# Decoup_Cap_1.net
KiCad netlist of a schematic drawn in Altium Designer
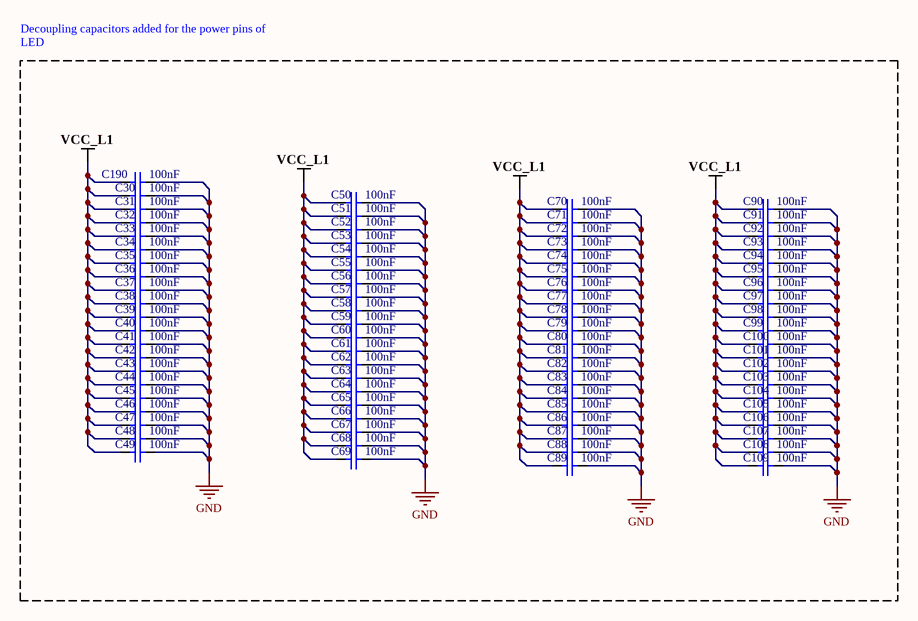
[diagram p0: Decoup_Cap 1.SchDoc]

(export (version "E")
  (design (tool "Eeschema 10.0.6"))
  (components
    (comp (ref "C30")
      (value "100nF")
      (footprint "Cap0402")
      (description "CAP CER 0.1UF 25V X7R 0402")
      (fields
        (field (name "MANUFACTURER") "Yageo")
        (field (name "MANUFACTURER PART NUMBER") "CC0402KRX7R8BB104")
      )
      (libsource (lib "TT_IntLib") (part "CC0402KRX7R8BB104"))
    )
    (comp (ref "C31")
      (value "100nF")
      (footprint "Cap0402")
      (description "CAP CER 0.1UF 25V X7R 0402")
      (fields
        (field (name "MANUFACTURER") "Yageo")
        (field (name "MANUFACTURER PART NUMBER") "CC0402KRX7R8BB104")
      )
      (libsource (lib "TT_IntLib") (part "CC0402KRX7R8BB104"))
    )
    (comp (ref "C32")
      (value "100nF")
      (footprint "Cap0402")
      (description "CAP CER 0.1UF 25V X7R 0402")
      (fields
        (field (name "MANUFACTURER") "Yageo")
        (field (name "MANUFACTURER PART NUMBER") "CC0402KRX7R8BB104")
      )
      (libsource (lib "TT_IntLib") (part "CC0402KRX7R8BB104"))
    )
    (comp (ref "C33")
      (value "100nF")
      (footprint "Cap0402")
      (description "CAP CER 0.1UF 25V X7R 0402")
      (fields
        (field (name "MANUFACTURER") "Yageo")
        (field (name "MANUFACTURER PART NUMBER") "CC0402KRX7R8BB104")
      )
      (libsource (lib "TT_IntLib") (part "CC0402KRX7R8BB104"))
    )
    (comp (ref "C34")
      (value "100nF")
      (footprint "Cap0402")
      (description "CAP CER 0.1UF 25V X7R 0402")
      (fields
        (field (name "MANUFACTURER") "Yageo")
        (field (name "MANUFACTURER PART NUMBER") "CC0402KRX7R8BB104")
      )
      (libsource (lib "TT_IntLib") (part "CC0402KRX7R8BB104"))
    )
    (comp (ref "C35")
      (value "100nF")
      (footprint "Cap0402")
      (description "CAP CER 0.1UF 25V X7R 0402")
      (fields
        (field (name "MANUFACTURER") "Yageo")
        (field (name "MANUFACTURER PART NUMBER") "CC0402KRX7R8BB104")
      )
      (libsource (lib "TT_IntLib") (part "CC0402KRX7R8BB104"))
    )
    (comp (ref "C36")
      (value "100nF")
      (footprint "Cap0402")
      (description "CAP CER 0.1UF 25V X7R 0402")
      (fields
        (field (name "MANUFACTURER") "Yageo")
        (field (name "MANUFACTURER PART NUMBER") "CC0402KRX7R8BB104")
      )
      (libsource (lib "TT_IntLib") (part "CC0402KRX7R8BB104"))
    )
    (comp (ref "C37")
      (value "100nF")
      (footprint "Cap0402")
      (description "CAP CER 0.1UF 25V X7R 0402")
      (fields
        (field (name "MANUFACTURER") "Yageo")
        (field (name "MANUFACTURER PART NUMBER") "CC0402KRX7R8BB104")
      )
      (libsource (lib "TT_IntLib") (part "CC0402KRX7R8BB104"))
    )
    (comp (ref "C38")
      (value "100nF")
      (footprint "Cap0402")
      (description "CAP CER 0.1UF 25V X7R 0402")
      (fields
        (field (name "MANUFACTURER") "Yageo")
        (field (name "MANUFACTURER PART NUMBER") "CC0402KRX7R8BB104")
      )
      (libsource (lib "TT_IntLib") (part "CC0402KRX7R8BB104"))
    )
    (comp (ref "C39")
      (value "100nF")
      (footprint "Cap0402")
      (description "CAP CER 0.1UF 25V X7R 0402")
      (fields
        (field (name "MANUFACTURER") "Yageo")
        (field (name "MANUFACTURER PART NUMBER") "CC0402KRX7R8BB104")
      )
      (libsource (lib "TT_IntLib") (part "CC0402KRX7R8BB104"))
    )
    (comp (ref "C40")
      (value "100nF")
      (footprint "Cap0402")
      (description "CAP CER 0.1UF 25V X7R 0402")
      (fields
        (field (name "MANUFACTURER") "Yageo")
        (field (name "MANUFACTURER PART NUMBER") "CC0402KRX7R8BB104")
      )
      (libsource (lib "TT_IntLib") (part "CC0402KRX7R8BB104"))
    )
    (comp (ref "C41")
      (value "100nF")
      (footprint "Cap0402")
      (description "CAP CER 0.1UF 25V X7R 0402")
      (fields
        (field (name "MANUFACTURER") "Yageo")
        (field (name "MANUFACTURER PART NUMBER") "CC0402KRX7R8BB104")
      )
      (libsource (lib "TT_IntLib") (part "CC0402KRX7R8BB104"))
    )
    (comp (ref "C42")
      (value "100nF")
      (footprint "Cap0402")
      (description "CAP CER 0.1UF 25V X7R 0402")
      (fields
        (field (name "MANUFACTURER") "Yageo")
        (field (name "MANUFACTURER PART NUMBER") "CC0402KRX7R8BB104")
      )
      (libsource (lib "TT_IntLib") (part "CC0402KRX7R8BB104"))
    )
    (comp (ref "C43")
      (value "100nF")
      (footprint "Cap0402")
      (description "CAP CER 0.1UF 25V X7R 0402")
      (fields
        (field (name "MANUFACTURER") "Yageo")
        (field (name "MANUFACTURER PART NUMBER") "CC0402KRX7R8BB104")
      )
      (libsource (lib "TT_IntLib") (part "CC0402KRX7R8BB104"))
    )
    (comp (ref "C44")
      (value "100nF")
      (footprint "Cap0402")
      (description "CAP CER 0.1UF 25V X7R 0402")
      (fields
        (field (name "MANUFACTURER") "Yageo")
        (field (name "MANUFACTURER PART NUMBER") "CC0402KRX7R8BB104")
      )
      (libsource (lib "TT_IntLib") (part "CC0402KRX7R8BB104"))
    )
    (comp (ref "C45")
      (value "100nF")
      (footprint "Cap0402")
      (description "CAP CER 0.1UF 25V X7R 0402")
      (fields
        (field (name "MANUFACTURER") "Yageo")
        (field (name "MANUFACTURER PART NUMBER") "CC0402KRX7R8BB104")
      )
      (libsource (lib "TT_IntLib") (part "CC0402KRX7R8BB104"))
    )
    (comp (ref "C46")
      (value "100nF")
      (footprint "Cap0402")
      (description "CAP CER 0.1UF 25V X7R 0402")
      (fields
        (field (name "MANUFACTURER") "Yageo")
        (field (name "MANUFACTURER PART NUMBER") "CC0402KRX7R8BB104")
      )
      (libsource (lib "TT_IntLib") (part "CC0402KRX7R8BB104"))
    )
    (comp (ref "C47")
      (value "100nF")
      (footprint "Cap0402")
      (description "CAP CER 0.1UF 25V X7R 0402")
      (fields
        (field (name "MANUFACTURER") "Yageo")
        (field (name "MANUFACTURER PART NUMBER") "CC0402KRX7R8BB104")
      )
      (libsource (lib "TT_IntLib") (part "CC0402KRX7R8BB104"))
    )
    (comp (ref "C48")
      (value "100nF")
      (footprint "Cap0402")
      (description "CAP CER 0.1UF 25V X7R 0402")
      (fields
        (field (name "MANUFACTURER") "Yageo")
        (field (name "MANUFACTURER PART NUMBER") "CC0402KRX7R8BB104")
      )
      (libsource (lib "TT_IntLib") (part "CC0402KRX7R8BB104"))
    )
    (comp (ref "C49")
      (value "100nF")
      (footprint "Cap0402")
      (description "CAP CER 0.1UF 25V X7R 0402")
      (fields
        (field (name "MANUFACTURER") "Yageo")
        (field (name "MANUFACTURER PART NUMBER") "CC0402KRX7R8BB104")
      )
      (libsource (lib "TT_IntLib") (part "CC0402KRX7R8BB104"))
    )
    (comp (ref "C50")
      (value "100nF")
      (footprint "Cap0402")
      (description "CAP CER 0.1UF 25V X7R 0402")
      (fields
        (field (name "MANUFACTURER") "Yageo")
        (field (name "MANUFACTURER PART NUMBER") "CC0402KRX7R8BB104")
      )
      (libsource (lib "TT_IntLib") (part "CC0402KRX7R8BB104"))
    )
    (comp (ref "C51")
      (value "100nF")
      (footprint "Cap0402")
      (description "CAP CER 0.1UF 25V X7R 0402")
      (fields
        (field (name "MANUFACTURER") "Yageo")
        (field (name "MANUFACTURER PART NUMBER") "CC0402KRX7R8BB104")
      )
      (libsource (lib "TT_IntLib") (part "CC0402KRX7R8BB104"))
    )
    (comp (ref "C52")
      (value "100nF")
      (footprint "Cap0402")
      (description "CAP CER 0.1UF 25V X7R 0402")
      (fields
        (field (name "MANUFACTURER") "Yageo")
        (field (name "MANUFACTURER PART NUMBER") "CC0402KRX7R8BB104")
      )
      (libsource (lib "TT_IntLib") (part "CC0402KRX7R8BB104"))
    )
    (comp (ref "C53")
      (value "100nF")
      (footprint "Cap0402")
      (description "CAP CER 0.1UF 25V X7R 0402")
      (fields
        (field (name "MANUFACTURER") "Yageo")
        (field (name "MANUFACTURER PART NUMBER") "CC0402KRX7R8BB104")
      )
      (libsource (lib "TT_IntLib") (part "CC0402KRX7R8BB104"))
    )
    (comp (ref "C54")
      (value "100nF")
      (footprint "Cap0402")
      (description "CAP CER 0.1UF 25V X7R 0402")
      (fields
        (field (name "MANUFACTURER") "Yageo")
        (field (name "MANUFACTURER PART NUMBER") "CC0402KRX7R8BB104")
      )
      (libsource (lib "TT_IntLib") (part "CC0402KRX7R8BB104"))
    )
    (comp (ref "C55")
      (value "100nF")
      (footprint "Cap0402")
      (description "CAP CER 0.1UF 25V X7R 0402")
      (fields
        (field (name "MANUFACTURER") "Yageo")
        (field (name "MANUFACTURER PART NUMBER") "CC0402KRX7R8BB104")
      )
      (libsource (lib "TT_IntLib") (part "CC0402KRX7R8BB104"))
    )
    (comp (ref "C56")
      (value "100nF")
      (footprint "Cap0402")
      (description "CAP CER 0.1UF 25V X7R 0402")
      (fields
        (field (name "MANUFACTURER") "Yageo")
        (field (name "MANUFACTURER PART NUMBER") "CC0402KRX7R8BB104")
      )
      (libsource (lib "TT_IntLib") (part "CC0402KRX7R8BB104"))
    )
    (comp (ref "C57")
      (value "100nF")
      (footprint "Cap0402")
      (description "CAP CER 0.1UF 25V X7R 0402")
      (fields
        (field (name "MANUFACTURER") "Yageo")
        (field (name "MANUFACTURER PART NUMBER") "CC0402KRX7R8BB104")
      )
      (libsource (lib "TT_IntLib") (part "CC0402KRX7R8BB104"))
    )
    (comp (ref "C58")
      (value "100nF")
      (footprint "Cap0402")
      (description "CAP CER 0.1UF 25V X7R 0402")
      (fields
        (field (name "MANUFACTURER") "Yageo")
        (field (name "MANUFACTURER PART NUMBER") "CC0402KRX7R8BB104")
      )
      (libsource (lib "TT_IntLib") (part "CC0402KRX7R8BB104"))
    )
    (comp (ref "C59")
      (value "100nF")
      (footprint "Cap0402")
      (description "CAP CER 0.1UF 25V X7R 0402")
      (fields
        (field (name "MANUFACTURER") "Yageo")
        (field (name "MANUFACTURER PART NUMBER") "CC0402KRX7R8BB104")
      )
      (libsource (lib "TT_IntLib") (part "CC0402KRX7R8BB104"))
    )
    (comp (ref "C60")
      (value "100nF")
      (footprint "Cap0402")
      (description "CAP CER 0.1UF 25V X7R 0402")
      (fields
        (field (name "MANUFACTURER") "Yageo")
        (field (name "MANUFACTURER PART NUMBER") "CC0402KRX7R8BB104")
      )
      (libsource (lib "TT_IntLib") (part "CC0402KRX7R8BB104"))
    )
    (comp (ref "C61")
      (value "100nF")
      (footprint "Cap0402")
      (description "CAP CER 0.1UF 25V X7R 0402")
      (fields
        (field (name "MANUFACTURER") "Yageo")
        (field (name "MANUFACTURER PART NUMBER") "CC0402KRX7R8BB104")
      )
      (libsource (lib "TT_IntLib") (part "CC0402KRX7R8BB104"))
    )
    (comp (ref "C62")
      (value "100nF")
      (footprint "Cap0402")
      (description "CAP CER 0.1UF 25V X7R 0402")
      (fields
        (field (name "MANUFACTURER") "Yageo")
        (field (name "MANUFACTURER PART NUMBER") "CC0402KRX7R8BB104")
      )
      (libsource (lib "TT_IntLib") (part "CC0402KRX7R8BB104"))
    )
    (comp (ref "C63")
      (value "100nF")
      (footprint "Cap0402")
      (description "CAP CER 0.1UF 25V X7R 0402")
      (fields
        (field (name "MANUFACTURER") "Yageo")
        (field (name "MANUFACTURER PART NUMBER") "CC0402KRX7R8BB104")
      )
      (libsource (lib "TT_IntLib") (part "CC0402KRX7R8BB104"))
    )
    (comp (ref "C64")
      (value "100nF")
      (footprint "Cap0402")
      (description "CAP CER 0.1UF 25V X7R 0402")
      (fields
        (field (name "MANUFACTURER") "Yageo")
        (field (name "MANUFACTURER PART NUMBER") "CC0402KRX7R8BB104")
      )
      (libsource (lib "TT_IntLib") (part "CC0402KRX7R8BB104"))
    )
    (comp (ref "C65")
      (value "100nF")
      (footprint "Cap0402")
      (description "CAP CER 0.1UF 25V X7R 0402")
      (fields
        (field (name "MANUFACTURER") "Yageo")
        (field (name "MANUFACTURER PART NUMBER") "CC0402KRX7R8BB104")
      )
      (libsource (lib "TT_IntLib") (part "CC0402KRX7R8BB104"))
    )
    (comp (ref "C66")
      (value "100nF")
      (footprint "Cap0402")
      (description "CAP CER 0.1UF 25V X7R 0402")
      (fields
        (field (name "MANUFACTURER") "Yageo")
        (field (name "MANUFACTURER PART NUMBER") "CC0402KRX7R8BB104")
      )
      (libsource (lib "TT_IntLib") (part "CC0402KRX7R8BB104"))
    )
    (comp (ref "C67")
      (value "100nF")
      (footprint "Cap0402")
      (description "CAP CER 0.1UF 25V X7R 0402")
      (fields
        (field (name "MANUFACTURER") "Yageo")
        (field (name "MANUFACTURER PART NUMBER") "CC0402KRX7R8BB104")
      )
      (libsource (lib "TT_IntLib") (part "CC0402KRX7R8BB104"))
    )
    (comp (ref "C68")
      (value "100nF")
      (footprint "Cap0402")
      (description "CAP CER 0.1UF 25V X7R 0402")
      (fields
        (field (name "MANUFACTURER") "Yageo")
        (field (name "MANUFACTURER PART NUMBER") "CC0402KRX7R8BB104")
      )
      (libsource (lib "TT_IntLib") (part "CC0402KRX7R8BB104"))
    )
    (comp (ref "C69")
      (value "100nF")
      (footprint "Cap0402")
      (description "CAP CER 0.1UF 25V X7R 0402")
      (fields
        (field (name "MANUFACTURER") "Yageo")
        (field (name "MANUFACTURER PART NUMBER") "CC0402KRX7R8BB104")
      )
      (libsource (lib "TT_IntLib") (part "CC0402KRX7R8BB104"))
    )
    (comp (ref "C70")
      (value "100nF")
      (footprint "Cap0402")
      (description "CAP CER 0.1UF 25V X7R 0402")
      (fields
        (field (name "MANUFACTURER") "Yageo")
        (field (name "MANUFACTURER PART NUMBER") "CC0402KRX7R8BB104")
      )
      (libsource (lib "TT_IntLib") (part "CC0402KRX7R8BB104"))
    )
    (comp (ref "C71")
      (value "100nF")
      (footprint "Cap0402")
      (description "CAP CER 0.1UF 25V X7R 0402")
      (fields
        (field (name "MANUFACTURER") "Yageo")
        (field (name "MANUFACTURER PART NUMBER") "CC0402KRX7R8BB104")
      )
      (libsource (lib "TT_IntLib") (part "CC0402KRX7R8BB104"))
    )
    (comp (ref "C72")
      (value "100nF")
      (footprint "Cap0402")
      (description "CAP CER 0.1UF 25V X7R 0402")
      (fields
        (field (name "MANUFACTURER") "Yageo")
        (field (name "MANUFACTURER PART NUMBER") "CC0402KRX7R8BB104")
      )
      (libsource (lib "TT_IntLib") (part "CC0402KRX7R8BB104"))
    )
    (comp (ref "C73")
      (value "100nF")
      (footprint "Cap0402")
      (description "CAP CER 0.1UF 25V X7R 0402")
      (fields
        (field (name "MANUFACTURER") "Yageo")
        (field (name "MANUFACTURER PART NUMBER") "CC0402KRX7R8BB104")
      )
      (libsource (lib "TT_IntLib") (part "CC0402KRX7R8BB104"))
    )
    (comp (ref "C74")
      (value "100nF")
      (footprint "Cap0402")
      (description "CAP CER 0.1UF 25V X7R 0402")
      (fields
        (field (name "MANUFACTURER") "Yageo")
        (field (name "MANUFACTURER PART NUMBER") "CC0402KRX7R8BB104")
      )
      (libsource (lib "TT_IntLib") (part "CC0402KRX7R8BB104"))
    )
    (comp (ref "C75")
      (value "100nF")
      (footprint "Cap0402")
      (description "CAP CER 0.1UF 25V X7R 0402")
      (fields
        (field (name "MANUFACTURER") "Yageo")
        (field (name "MANUFACTURER PART NUMBER") "CC0402KRX7R8BB104")
      )
      (libsource (lib "TT_IntLib") (part "CC0402KRX7R8BB104"))
    )
    (comp (ref "C76")
      (value "100nF")
      (footprint "Cap0402")
      (description "CAP CER 0.1UF 25V X7R 0402")
      (fields
        (field (name "MANUFACTURER") "Yageo")
        (field (name "MANUFACTURER PART NUMBER") "CC0402KRX7R8BB104")
      )
      (libsource (lib "TT_IntLib") (part "CC0402KRX7R8BB104"))
    )
    (comp (ref "C77")
      (value "100nF")
      (footprint "Cap0402")
      (description "CAP CER 0.1UF 25V X7R 0402")
      (fields
        (field (name "MANUFACTURER") "Yageo")
        (field (name "MANUFACTURER PART NUMBER") "CC0402KRX7R8BB104")
      )
      (libsource (lib "TT_IntLib") (part "CC0402KRX7R8BB104"))
    )
    (comp (ref "C78")
      (value "100nF")
      (footprint "Cap0402")
      (description "CAP CER 0.1UF 25V X7R 0402")
      (fields
        (field (name "MANUFACTURER") "Yageo")
        (field (name "MANUFACTURER PART NUMBER") "CC0402KRX7R8BB104")
      )
      (libsource (lib "TT_IntLib") (part "CC0402KRX7R8BB104"))
    )
    (comp (ref "C79")
      (value "100nF")
      (footprint "Cap0402")
      (description "CAP CER 0.1UF 25V X7R 0402")
      (fields
        (field (name "MANUFACTURER") "Yageo")
        (field (name "MANUFACTURER PART NUMBER") "CC0402KRX7R8BB104")
      )
      (libsource (lib "TT_IntLib") (part "CC0402KRX7R8BB104"))
    )
    (comp (ref "C80")
      (value "100nF")
      (footprint "Cap0402")
      (description "CAP CER 0.1UF 25V X7R 0402")
      (fields
        (field (name "MANUFACTURER") "Yageo")
        (field (name "MANUFACTURER PART NUMBER") "CC0402KRX7R8BB104")
      )
      (libsource (lib "TT_IntLib") (part "CC0402KRX7R8BB104"))
    )
    (comp (ref "C81")
      (value "100nF")
      (footprint "Cap0402")
      (description "CAP CER 0.1UF 25V X7R 0402")
      (fields
        (field (name "MANUFACTURER") "Yageo")
        (field (name "MANUFACTURER PART NUMBER") "CC0402KRX7R8BB104")
      )
      (libsource (lib "TT_IntLib") (part "CC0402KRX7R8BB104"))
    )
    (comp (ref "C82")
      (value "100nF")
      (footprint "Cap0402")
      (description "CAP CER 0.1UF 25V X7R 0402")
      (fields
        (field (name "MANUFACTURER") "Yageo")
        (field (name "MANUFACTURER PART NUMBER") "CC0402KRX7R8BB104")
      )
      (libsource (lib "TT_IntLib") (part "CC0402KRX7R8BB104"))
    )
    (comp (ref "C83")
      (value "100nF")
      (footprint "Cap0402")
      (description "CAP CER 0.1UF 25V X7R 0402")
      (fields
        (field (name "MANUFACTURER") "Yageo")
        (field (name "MANUFACTURER PART NUMBER") "CC0402KRX7R8BB104")
      )
      (libsource (lib "TT_IntLib") (part "CC0402KRX7R8BB104"))
    )
    (comp (ref "C84")
      (value "100nF")
      (footprint "Cap0402")
      (description "CAP CER 0.1UF 25V X7R 0402")
      (fields
        (field (name "MANUFACTURER") "Yageo")
        (field (name "MANUFACTURER PART NUMBER") "CC0402KRX7R8BB104")
      )
      (libsource (lib "TT_IntLib") (part "CC0402KRX7R8BB104"))
    )
    (comp (ref "C85")
      (value "100nF")
      (footprint "Cap0402")
      (description "CAP CER 0.1UF 25V X7R 0402")
      (fields
        (field (name "MANUFACTURER") "Yageo")
        (field (name "MANUFACTURER PART NUMBER") "CC0402KRX7R8BB104")
      )
      (libsource (lib "TT_IntLib") (part "CC0402KRX7R8BB104"))
    )
    (comp (ref "C86")
      (value "100nF")
      (footprint "Cap0402")
      (description "CAP CER 0.1UF 25V X7R 0402")
      (fields
        (field (name "MANUFACTURER") "Yageo")
        (field (name "MANUFACTURER PART NUMBER") "CC0402KRX7R8BB104")
      )
      (libsource (lib "TT_IntLib") (part "CC0402KRX7R8BB104"))
    )
    (comp (ref "C87")
      (value "100nF")
      (footprint "Cap0402")
      (description "CAP CER 0.1UF 25V X7R 0402")
      (fields
        (field (name "MANUFACTURER") "Yageo")
        (field (name "MANUFACTURER PART NUMBER") "CC0402KRX7R8BB104")
      )
      (libsource (lib "TT_IntLib") (part "CC0402KRX7R8BB104"))
    )
    (comp (ref "C88")
      (value "100nF")
      (footprint "Cap0402")
      (description "CAP CER 0.1UF 25V X7R 0402")
      (fields
        (field (name "MANUFACTURER") "Yageo")
        (field (name "MANUFACTURER PART NUMBER") "CC0402KRX7R8BB104")
      )
      (libsource (lib "TT_IntLib") (part "CC0402KRX7R8BB104"))
    )
    (comp (ref "C89")
      (value "100nF")
      (footprint "Cap0402")
      (description "CAP CER 0.1UF 25V X7R 0402")
      (fields
        (field (name "MANUFACTURER") "Yageo")
        (field (name "MANUFACTURER PART NUMBER") "CC0402KRX7R8BB104")
      )
      (libsource (lib "TT_IntLib") (part "CC0402KRX7R8BB104"))
    )
    (comp (ref "C90")
      (value "100nF")
      (footprint "Cap0402")
      (description "CAP CER 0.1UF 25V X7R 0402")
      (fields
        (field (name "MANUFACTURER") "Yageo")
        (field (name "MANUFACTURER PART NUMBER") "CC0402KRX7R8BB104")
      )
      (libsource (lib "TT_IntLib") (part "CC0402KRX7R8BB104"))
    )
    (comp (ref "C91")
      (value "100nF")
      (footprint "Cap0402")
      (description "CAP CER 0.1UF 25V X7R 0402")
      (fields
        (field (name "MANUFACTURER") "Yageo")
        (field (name "MANUFACTURER PART NUMBER") "CC0402KRX7R8BB104")
      )
      (libsource (lib "TT_IntLib") (part "CC0402KRX7R8BB104"))
    )
    (comp (ref "C92")
      (value "100nF")
      (footprint "Cap0402")
      (description "CAP CER 0.1UF 25V X7R 0402")
      (fields
        (field (name "MANUFACTURER") "Yageo")
        (field (name "MANUFACTURER PART NUMBER") "CC0402KRX7R8BB104")
      )
      (libsource (lib "TT_IntLib") (part "CC0402KRX7R8BB104"))
    )
    (comp (ref "C93")
      (value "100nF")
      (footprint "Cap0402")
      (description "CAP CER 0.1UF 25V X7R 0402")
      (fields
        (field (name "MANUFACTURER") "Yageo")
        (field (name "MANUFACTURER PART NUMBER") "CC0402KRX7R8BB104")
      )
      (libsource (lib "TT_IntLib") (part "CC0402KRX7R8BB104"))
    )
    (comp (ref "C94")
      (value "100nF")
      (footprint "Cap0402")
      (description "CAP CER 0.1UF 25V X7R 0402")
      (fields
        (field (name "MANUFACTURER") "Yageo")
        (field (name "MANUFACTURER PART NUMBER") "CC0402KRX7R8BB104")
      )
      (libsource (lib "TT_IntLib") (part "CC0402KRX7R8BB104"))
    )
    (comp (ref "C95")
      (value "100nF")
      (footprint "Cap0402")
      (description "CAP CER 0.1UF 25V X7R 0402")
      (fields
        (field (name "MANUFACTURER") "Yageo")
        (field (name "MANUFACTURER PART NUMBER") "CC0402KRX7R8BB104")
      )
      (libsource (lib "TT_IntLib") (part "CC0402KRX7R8BB104"))
    )
    (comp (ref "C96")
      (value "100nF")
      (footprint "Cap0402")
      (description "CAP CER 0.1UF 25V X7R 0402")
      (fields
        (field (name "MANUFACTURER") "Yageo")
        (field (name "MANUFACTURER PART NUMBER") "CC0402KRX7R8BB104")
      )
      (libsource (lib "TT_IntLib") (part "CC0402KRX7R8BB104"))
    )
    (comp (ref "C97")
      (value "100nF")
      (footprint "Cap0402")
      (description "CAP CER 0.1UF 25V X7R 0402")
      (fields
        (field (name "MANUFACTURER") "Yageo")
        (field (name "MANUFACTURER PART NUMBER") "CC0402KRX7R8BB104")
      )
      (libsource (lib "TT_IntLib") (part "CC0402KRX7R8BB104"))
    )
    (comp (ref "C98")
      (value "100nF")
      (footprint "Cap0402")
      (description "CAP CER 0.1UF 25V X7R 0402")
      (fields
        (field (name "MANUFACTURER") "Yageo")
        (field (name "MANUFACTURER PART NUMBER") "CC0402KRX7R8BB104")
      )
      (libsource (lib "TT_IntLib") (part "CC0402KRX7R8BB104"))
    )
    (comp (ref "C99")
      (value "100nF")
      (footprint "Cap0402")
      (description "CAP CER 0.1UF 25V X7R 0402")
      (fields
        (field (name "MANUFACTURER") "Yageo")
        (field (name "MANUFACTURER PART NUMBER") "CC0402KRX7R8BB104")
      )
      (libsource (lib "TT_IntLib") (part "CC0402KRX7R8BB104"))
    )
    (comp (ref "C100")
      (value "100nF")
      (footprint "Cap0402")
      (description "CAP CER 0.1UF 25V X7R 0402")
      (fields
        (field (name "MANUFACTURER") "Yageo")
        (field (name "MANUFACTURER PART NUMBER") "CC0402KRX7R8BB104")
      )
      (libsource (lib "TT_IntLib") (part "CC0402KRX7R8BB104"))
    )
    (comp (ref "C101")
      (value "100nF")
      (footprint "Cap0402")
      (description "CAP CER 0.1UF 25V X7R 0402")
      (fields
        (field (name "MANUFACTURER") "Yageo")
        (field (name "MANUFACTURER PART NUMBER") "CC0402KRX7R8BB104")
      )
      (libsource (lib "TT_IntLib") (part "CC0402KRX7R8BB104"))
    )
    (comp (ref "C102")
      (value "100nF")
      (footprint "Cap0402")
      (description "CAP CER 0.1UF 25V X7R 0402")
      (fields
        (field (name "MANUFACTURER") "Yageo")
        (field (name "MANUFACTURER PART NUMBER") "CC0402KRX7R8BB104")
      )
      (libsource (lib "TT_IntLib") (part "CC0402KRX7R8BB104"))
    )
    (comp (ref "C103")
      (value "100nF")
      (footprint "Cap0402")
      (description "CAP CER 0.1UF 25V X7R 0402")
      (fields
        (field (name "MANUFACTURER") "Yageo")
        (field (name "MANUFACTURER PART NUMBER") "CC0402KRX7R8BB104")
      )
      (libsource (lib "TT_IntLib") (part "CC0402KRX7R8BB104"))
    )
    (comp (ref "C104")
      (value "100nF")
      (footprint "Cap0402")
      (description "CAP CER 0.1UF 25V X7R 0402")
      (fields
        (field (name "MANUFACTURER") "Yageo")
        (field (name "MANUFACTURER PART NUMBER") "CC0402KRX7R8BB104")
      )
      (libsource (lib "TT_IntLib") (part "CC0402KRX7R8BB104"))
    )
    (comp (ref "C105")
      (value "100nF")
      (footprint "Cap0402")
      (description "CAP CER 0.1UF 25V X7R 0402")
      (fields
        (field (name "MANUFACTURER") "Yageo")
        (field (name "MANUFACTURER PART NUMBER") "CC0402KRX7R8BB104")
      )
      (libsource (lib "TT_IntLib") (part "CC0402KRX7R8BB104"))
    )
    (comp (ref "C106")
      (value "100nF")
      (footprint "Cap0402")
      (description "CAP CER 0.1UF 25V X7R 0402")
      (fields
        (field (name "MANUFACTURER") "Yageo")
        (field (name "MANUFACTURER PART NUMBER") "CC0402KRX7R8BB104")
      )
      (libsource (lib "TT_IntLib") (part "CC0402KRX7R8BB104"))
    )
    (comp (ref "C107")
      (value "100nF")
      (footprint "Cap0402")
      (description "CAP CER 0.1UF 25V X7R 0402")
      (fields
        (field (name "MANUFACTURER") "Yageo")
        (field (name "MANUFACTURER PART NUMBER") "CC0402KRX7R8BB104")
      )
      (libsource (lib "TT_IntLib") (part "CC0402KRX7R8BB104"))
    )
    (comp (ref "C108")
      (value "100nF")
      (footprint "Cap0402")
      (description "CAP CER 0.1UF 25V X7R 0402")
      (fields
        (field (name "MANUFACTURER") "Yageo")
        (field (name "MANUFACTURER PART NUMBER") "CC0402KRX7R8BB104")
      )
      (libsource (lib "TT_IntLib") (part "CC0402KRX7R8BB104"))
    )
    (comp (ref "C109")
      (value "100nF")
      (footprint "Cap0402")
      (description "CAP CER 0.1UF 25V X7R 0402")
      (fields
        (field (name "MANUFACTURER") "Yageo")
        (field (name "MANUFACTURER PART NUMBER") "CC0402KRX7R8BB104")
      )
      (libsource (lib "TT_IntLib") (part "CC0402KRX7R8BB104"))
    )
    (comp (ref "C190")
      (value "100nF")
      (footprint "Cap0402")
      (description "CAP CER 0.1UF 25V X7R 0402")
      (fields
        (field (name "MANUFACTURER") "Yageo")
        (field (name "MANUFACTURER PART NUMBER") "CC0402KRX7R8BB104")
      )
      (libsource (lib "TT_IntLib") (part "CC0402KRX7R8BB104"))
    )
  )
  (nets
    (net (code "1") (name "GND") (class "Default")
      (node (ref "C100") (pin "1") (pintype "passive"))
      (node (ref "C101") (pin "1") (pintype "passive"))
      (node (ref "C102") (pin "1") (pintype "passive"))
      (node (ref "C103") (pin "1") (pintype "passive"))
      (node (ref "C104") (pin "1") (pintype "passive"))
      (node (ref "C105") (pin "1") (pintype "passive"))
      (node (ref "C106") (pin "1") (pintype "passive"))
      (node (ref "C107") (pin "1") (pintype "passive"))
      (node (ref "C108") (pin "1") (pintype "passive"))
      (node (ref "C109") (pin "1") (pintype "passive"))
      (node (ref "C190") (pin "1") (pintype "passive"))
      (node (ref "C30") (pin "1") (pintype "passive"))
      (node (ref "C31") (pin "1") (pintype "passive"))
      (node (ref "C32") (pin "1") (pintype "passive"))
      (node (ref "C33") (pin "1") (pintype "passive"))
      (node (ref "C34") (pin "1") (pintype "passive"))
      (node (ref "C35") (pin "1") (pintype "passive"))
      (node (ref "C36") (pin "1") (pintype "passive"))
      (node (ref "C37") (pin "1") (pintype "passive"))
      (node (ref "C38") (pin "1") (pintype "passive"))
      (node (ref "C39") (pin "1") (pintype "passive"))
      (node (ref "C40") (pin "1") (pintype "passive"))
      (node (ref "C41") (pin "1") (pintype "passive"))
      (node (ref "C42") (pin "1") (pintype "passive"))
      (node (ref "C43") (pin "1") (pintype "passive"))
      (node (ref "C44") (pin "1") (pintype "passive"))
      (node (ref "C45") (pin "1") (pintype "passive"))
      (node (ref "C46") (pin "1") (pintype "passive"))
      (node (ref "C47") (pin "1") (pintype "passive"))
      (node (ref "C48") (pin "1") (pintype "passive"))
      (node (ref "C49") (pin "1") (pintype "passive"))
      (node (ref "C50") (pin "1") (pintype "passive"))
      (node (ref "C51") (pin "1") (pintype "passive"))
      (node (ref "C52") (pin "1") (pintype "passive"))
      (node (ref "C53") (pin "1") (pintype "passive"))
      (node (ref "C54") (pin "1") (pintype "passive"))
      (node (ref "C55") (pin "1") (pintype "passive"))
      (node (ref "C56") (pin "1") (pintype "passive"))
      (node (ref "C57") (pin "1") (pintype "passive"))
      (node (ref "C58") (pin "1") (pintype "passive"))
      (node (ref "C59") (pin "1") (pintype "passive"))
      (node (ref "C60") (pin "1") (pintype "passive"))
      (node (ref "C61") (pin "1") (pintype "passive"))
      (node (ref "C62") (pin "1") (pintype "passive"))
      (node (ref "C63") (pin "1") (pintype "passive"))
      (node (ref "C64") (pin "1") (pintype "passive"))
      (node (ref "C65") (pin "1") (pintype "passive"))
      (node (ref "C66") (pin "1") (pintype "passive"))
      (node (ref "C67") (pin "1") (pintype "passive"))
      (node (ref "C68") (pin "1") (pintype "passive"))
      (node (ref "C69") (pin "1") (pintype "passive"))
      (node (ref "C70") (pin "1") (pintype "passive"))
      (node (ref "C71") (pin "1") (pintype "passive"))
      (node (ref "C72") (pin "1") (pintype "passive"))
      (node (ref "C73") (pin "1") (pintype "passive"))
      (node (ref "C74") (pin "1") (pintype "passive"))
      (node (ref "C75") (pin "1") (pintype "passive"))
      (node (ref "C76") (pin "1") (pintype "passive"))
      (node (ref "C77") (pin "1") (pintype "passive"))
      (node (ref "C78") (pin "1") (pintype "passive"))
      (node (ref "C79") (pin "1") (pintype "passive"))
      (node (ref "C80") (pin "1") (pintype "passive"))
      (node (ref "C81") (pin "1") (pintype "passive"))
      (node (ref "C82") (pin "1") (pintype "passive"))
      (node (ref "C83") (pin "1") (pintype "passive"))
      (node (ref "C84") (pin "1") (pintype "passive"))
      (node (ref "C85") (pin "1") (pintype "passive"))
      (node (ref "C86") (pin "1") (pintype "passive"))
      (node (ref "C87") (pin "1") (pintype "passive"))
      (node (ref "C88") (pin "1") (pintype "passive"))
      (node (ref "C89") (pin "1") (pintype "passive"))
      (node (ref "C90") (pin "1") (pintype "passive"))
      (node (ref "C91") (pin "1") (pintype "passive"))
      (node (ref "C92") (pin "1") (pintype "passive"))
      (node (ref "C93") (pin "1") (pintype "passive"))
      (node (ref "C94") (pin "1") (pintype "passive"))
      (node (ref "C95") (pin "1") (pintype "passive"))
      (node (ref "C96") (pin "1") (pintype "passive"))
      (node (ref "C97") (pin "1") (pintype "passive"))
      (node (ref "C98") (pin "1") (pintype "passive"))
      (node (ref "C99") (pin "1") (pintype "passive"))
    )
    (net (code "2") (name "VCC_L1") (class "Default")
      (node (ref "C100") (pin "2") (pintype "passive"))
      (node (ref "C101") (pin "2") (pintype "passive"))
      (node (ref "C102") (pin "2") (pintype "passive"))
      (node (ref "C103") (pin "2") (pintype "passive"))
      (node (ref "C104") (pin "2") (pintype "passive"))
      (node (ref "C105") (pin "2") (pintype "passive"))
      (node (ref "C106") (pin "2") (pintype "passive"))
      (node (ref "C107") (pin "2") (pintype "passive"))
      (node (ref "C108") (pin "2") (pintype "passive"))
      (node (ref "C109") (pin "2") (pintype "passive"))
      (node (ref "C190") (pin "2") (pintype "passive"))
      (node (ref "C30") (pin "2") (pintype "passive"))
      (node (ref "C31") (pin "2") (pintype "passive"))
      (node (ref "C32") (pin "2") (pintype "passive"))
      (node (ref "C33") (pin "2") (pintype "passive"))
      (node (ref "C34") (pin "2") (pintype "passive"))
      (node (ref "C35") (pin "2") (pintype "passive"))
      (node (ref "C36") (pin "2") (pintype "passive"))
      (node (ref "C37") (pin "2") (pintype "passive"))
      (node (ref "C38") (pin "2") (pintype "passive"))
      (node (ref "C39") (pin "2") (pintype "passive"))
      (node (ref "C40") (pin "2") (pintype "passive"))
      (node (ref "C41") (pin "2") (pintype "passive"))
      (node (ref "C42") (pin "2") (pintype "passive"))
      (node (ref "C43") (pin "2") (pintype "passive"))
      (node (ref "C44") (pin "2") (pintype "passive"))
      (node (ref "C45") (pin "2") (pintype "passive"))
      (node (ref "C46") (pin "2") (pintype "passive"))
      (node (ref "C47") (pin "2") (pintype "passive"))
      (node (ref "C48") (pin "2") (pintype "passive"))
      (node (ref "C49") (pin "2") (pintype "passive"))
      (node (ref "C50") (pin "2") (pintype "passive"))
      (node (ref "C51") (pin "2") (pintype "passive"))
      (node (ref "C52") (pin "2") (pintype "passive"))
      (node (ref "C53") (pin "2") (pintype "passive"))
      (node (ref "C54") (pin "2") (pintype "passive"))
      (node (ref "C55") (pin "2") (pintype "passive"))
      (node (ref "C56") (pin "2") (pintype "passive"))
      (node (ref "C57") (pin "2") (pintype "passive"))
      (node (ref "C58") (pin "2") (pintype "passive"))
      (node (ref "C59") (pin "2") (pintype "passive"))
      (node (ref "C60") (pin "2") (pintype "passive"))
      (node (ref "C61") (pin "2") (pintype "passive"))
      (node (ref "C62") (pin "2") (pintype "passive"))
      (node (ref "C63") (pin "2") (pintype "passive"))
      (node (ref "C64") (pin "2") (pintype "passive"))
      (node (ref "C65") (pin "2") (pintype "passive"))
      (node (ref "C66") (pin "2") (pintype "passive"))
      (node (ref "C67") (pin "2") (pintype "passive"))
      (node (ref "C68") (pin "2") (pintype "passive"))
      (node (ref "C69") (pin "2") (pintype "passive"))
      (node (ref "C70") (pin "2") (pintype "passive"))
      (node (ref "C71") (pin "2") (pintype "passive"))
      (node (ref "C72") (pin "2") (pintype "passive"))
      (node (ref "C73") (pin "2") (pintype "passive"))
      (node (ref "C74") (pin "2") (pintype "passive"))
      (node (ref "C75") (pin "2") (pintype "passive"))
      (node (ref "C76") (pin "2") (pintype "passive"))
      (node (ref "C77") (pin "2") (pintype "passive"))
      (node (ref "C78") (pin "2") (pintype "passive"))
      (node (ref "C79") (pin "2") (pintype "passive"))
      (node (ref "C80") (pin "2") (pintype "passive"))
      (node (ref "C81") (pin "2") (pintype "passive"))
      (node (ref "C82") (pin "2") (pintype "passive"))
      (node (ref "C83") (pin "2") (pintype "passive"))
      (node (ref "C84") (pin "2") (pintype "passive"))
      (node (ref "C85") (pin "2") (pintype "passive"))
      (node (ref "C86") (pin "2") (pintype "passive"))
      (node (ref "C87") (pin "2") (pintype "passive"))
      (node (ref "C88") (pin "2") (pintype "passive"))
      (node (ref "C89") (pin "2") (pintype "passive"))
      (node (ref "C90") (pin "2") (pintype "passive"))
      (node (ref "C91") (pin "2") (pintype "passive"))
      (node (ref "C92") (pin "2") (pintype "passive"))
      (node (ref "C93") (pin "2") (pintype "passive"))
      (node (ref "C94") (pin "2") (pintype "passive"))
      (node (ref "C95") (pin "2") (pintype "passive"))
      (node (ref "C96") (pin "2") (pintype "passive"))
      (node (ref "C97") (pin "2") (pintype "passive"))
      (node (ref "C98") (pin "2") (pintype "passive"))
      (node (ref "C99") (pin "2") (pintype "passive"))
    )
  )
)
